# SSX.net
KiCad netlist of a schematic drawn in EAGLE
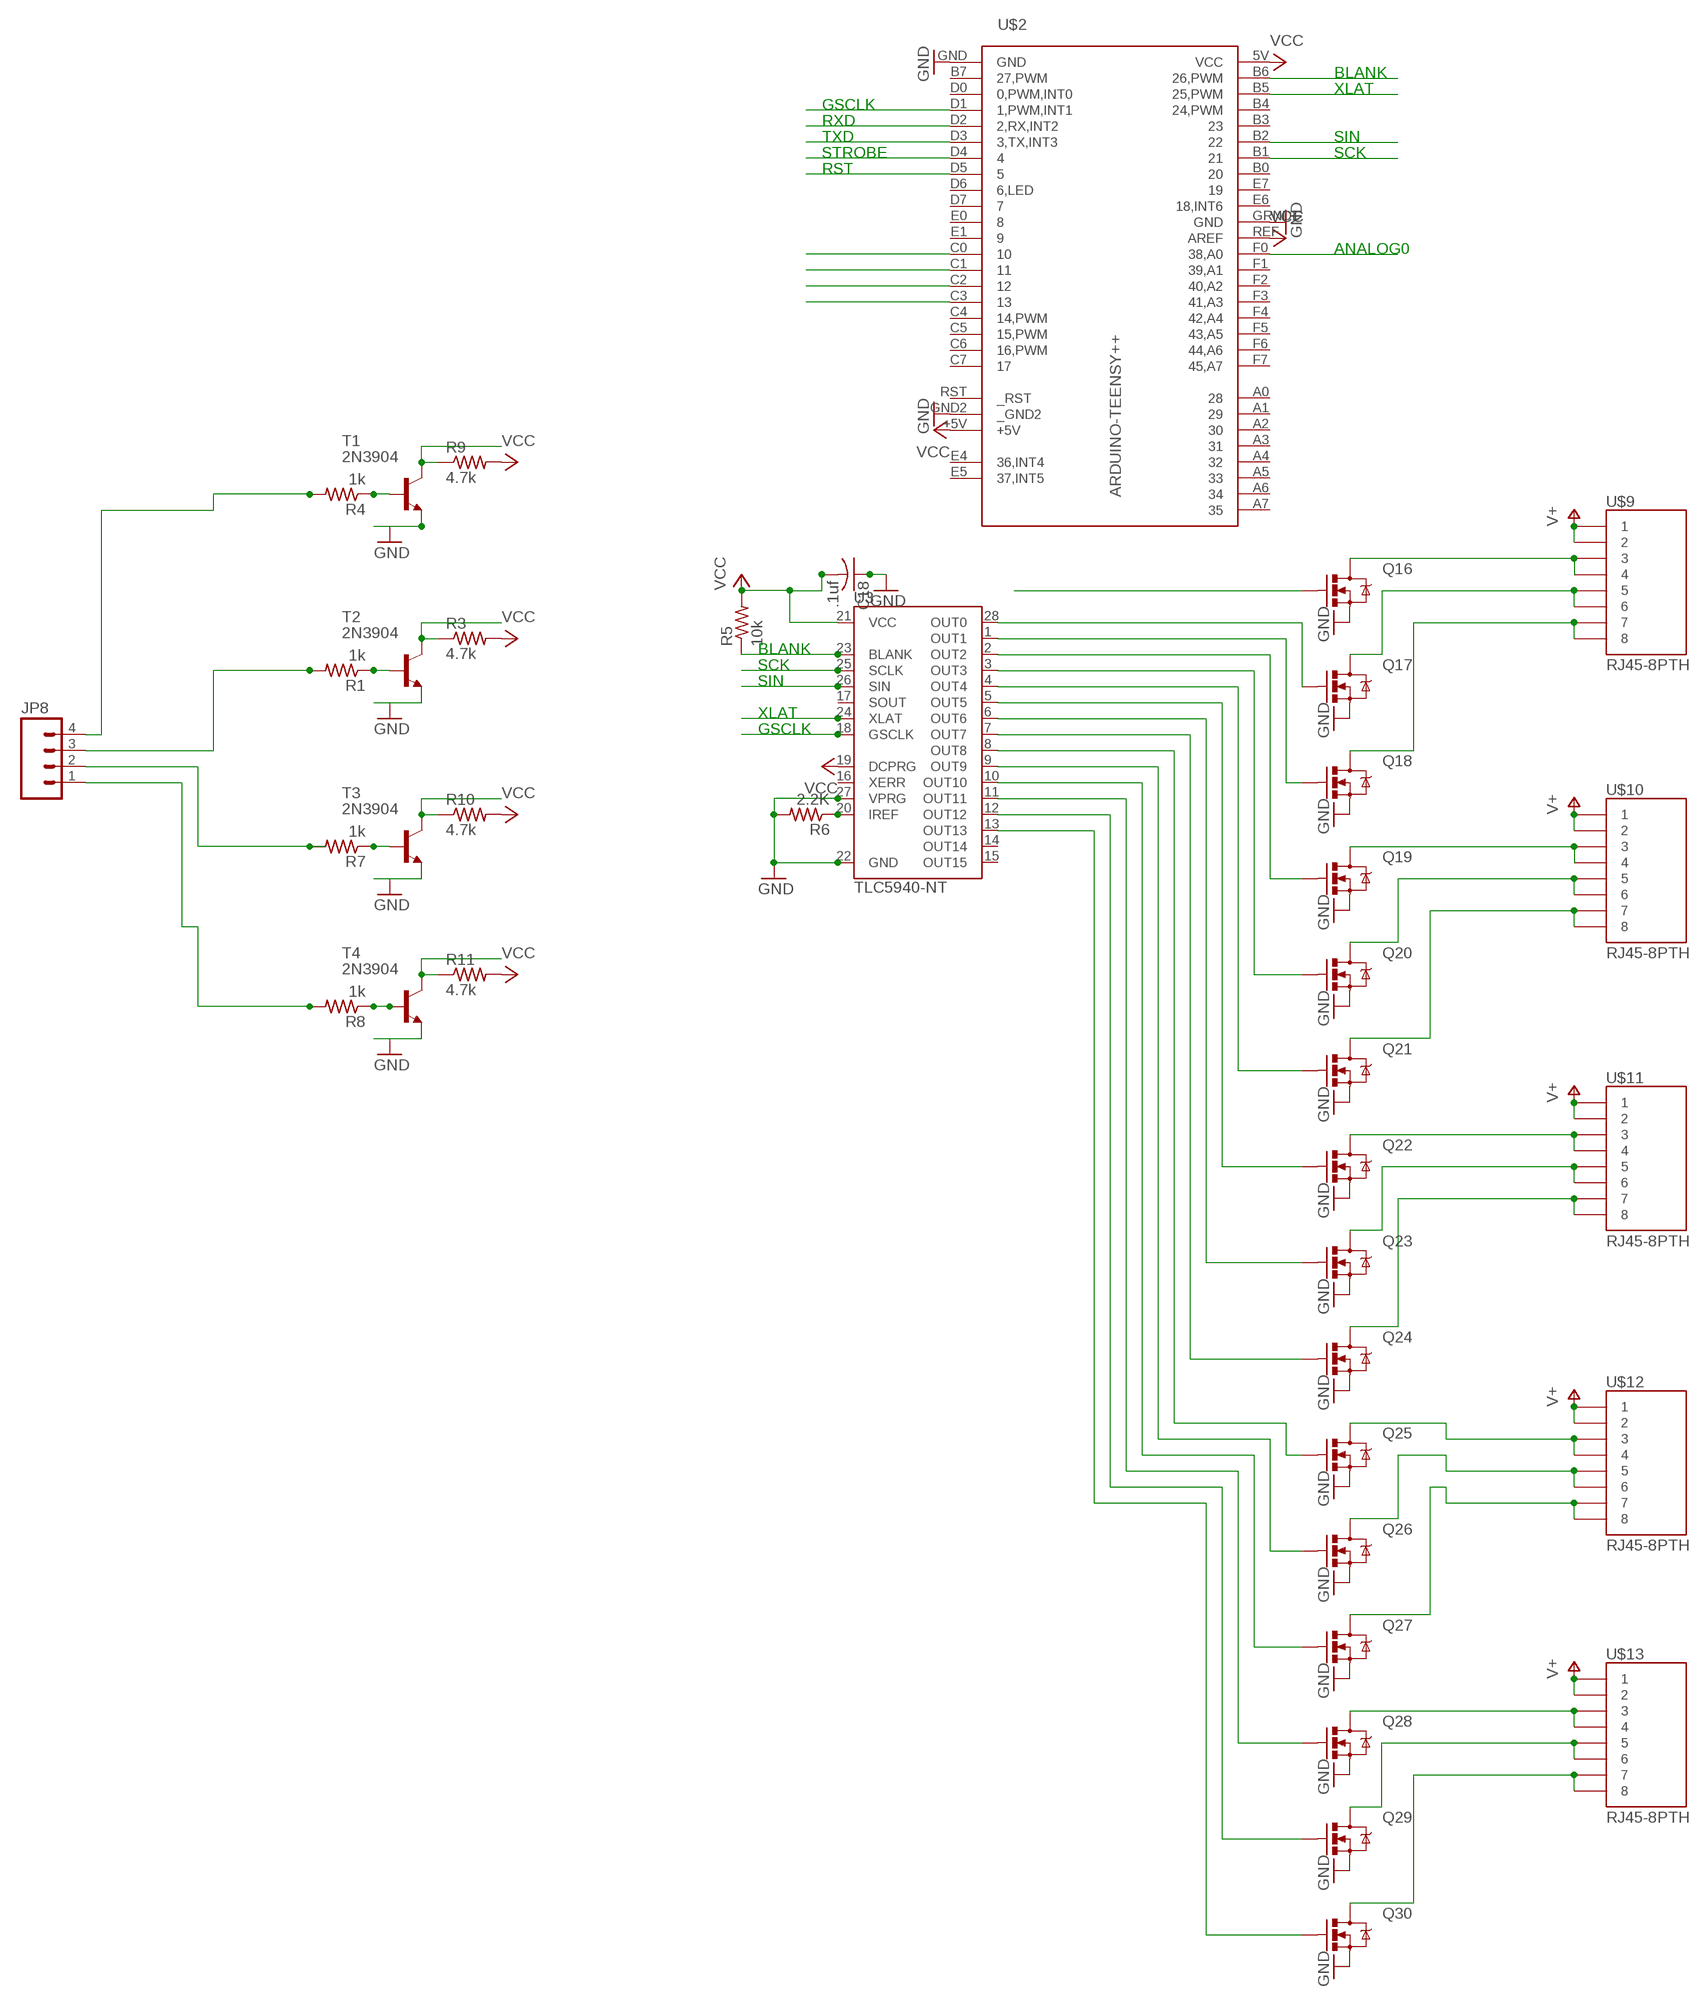
[diagram p0: schematic, sheet 1, part 1 of 2]
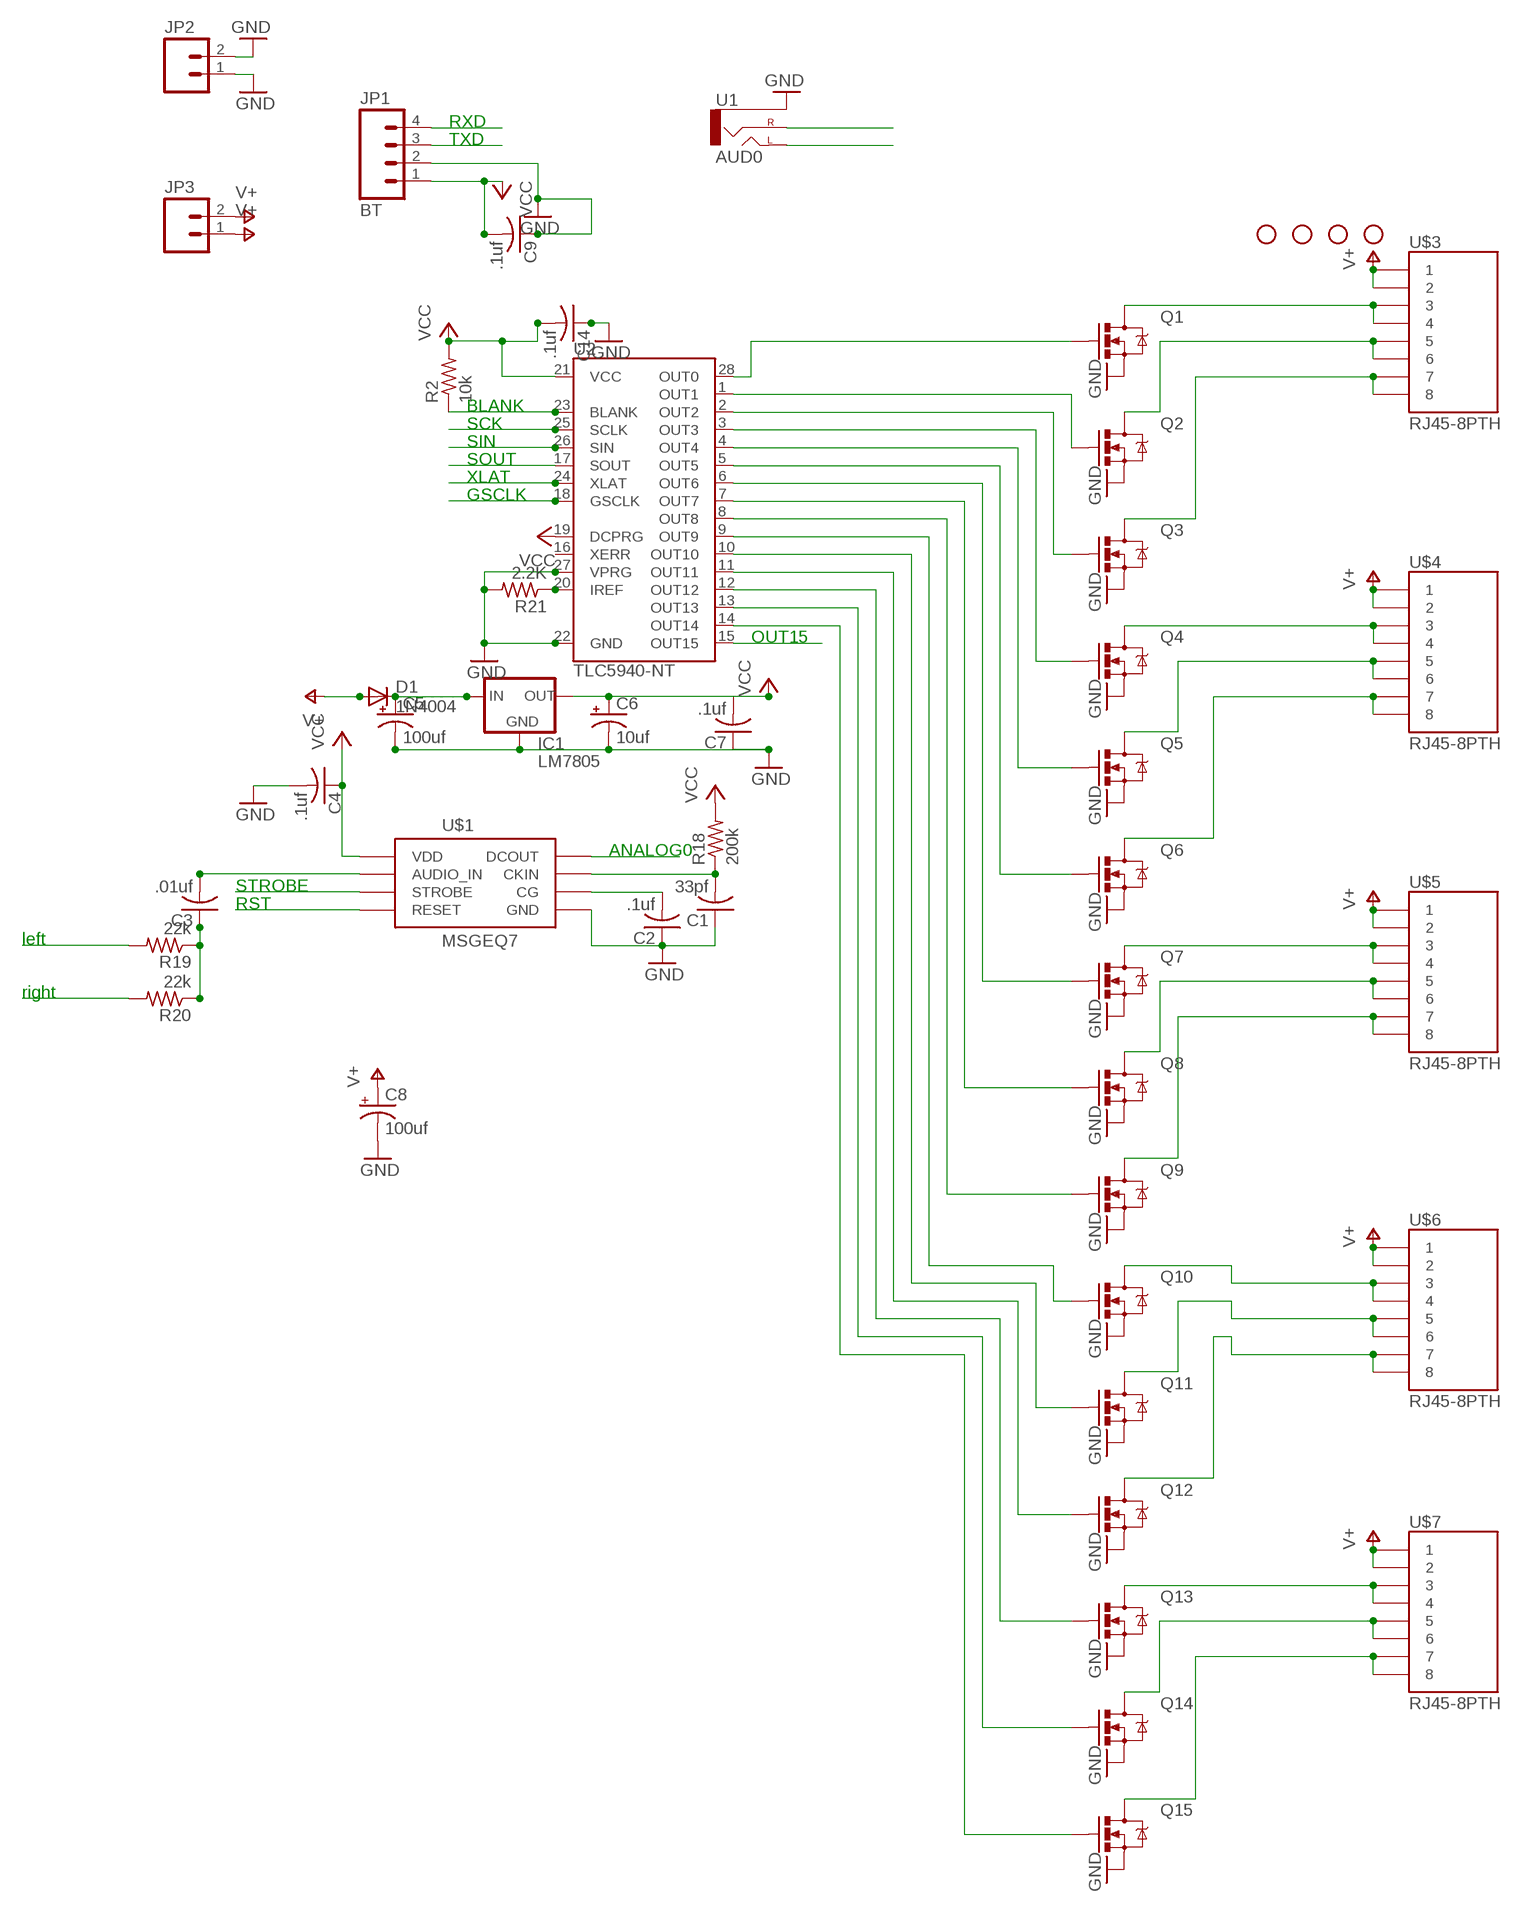
[diagram p1: schematic, sheet 1, part 2 of 2]

(export (version "E")
  (design (tool "Eeschema 10.0.6"))
  (components
    (comp (ref "C1")
      (value "33pf")
      (footprint "eagle-import:C025-025X050")
      (libsource (lib "eagle-import") (part "C-US025-025X050"))
    )
    (comp (ref "C2")
      (value ".1uf")
      (footprint "eagle-import:C025-025X050")
      (libsource (lib "eagle-import") (part "C-US025-025X050"))
    )
    (comp (ref "C3")
      (value ".01uf")
      (footprint "eagle-import:C025-025X050")
      (libsource (lib "eagle-import") (part "C-US025-025X050"))
    )
    (comp (ref "C4")
      (value ".1uf")
      (footprint "eagle-import:C025-025X050")
      (libsource (lib "eagle-import") (part "C-US025-025X050"))
    )
    (comp (ref "C5")
      (value "100uf")
      (footprint "eagle-import:CPOL-RADIAL-100UF-25V")
      (libsource (lib "eagle-import") (part "CAP_POLPTH1"))
    )
    (comp (ref "C6")
      (value "10uf")
      (footprint "eagle-import:CPOL-RADIAL-10UF-25V")
      (libsource (lib "eagle-import") (part "CAP_POLPTH2"))
    )
    (comp (ref "C7")
      (value ".1uf")
      (footprint "eagle-import:C025-025X050")
      (libsource (lib "eagle-import") (part "C-US025-025X050"))
    )
    (comp (ref "C8")
      (value "100uf")
      (footprint "eagle-import:CPOL-RADIAL-100UF-25V")
      (libsource (lib "eagle-import") (part "CAP_POLPTH1"))
    )
    (comp (ref "C9")
      (value ".1uf")
      (footprint "eagle-import:C025-025X050")
      (libsource (lib "eagle-import") (part "C-US025-025X050"))
    )
    (comp (ref "C14")
      (value ".1uf")
      (footprint "eagle-import:C025-025X050")
      (libsource (lib "eagle-import") (part "C-US025-025X050"))
    )
    (comp (ref "C18")
      (value ".1uf")
      (footprint "eagle-import:C025-025X050")
      (libsource (lib "eagle-import") (part "C-US025-025X050"))
    )
    (comp (ref "D1")
      (value "1N4004")
      (footprint "eagle-import:DIODE-1N4001")
      (libsource (lib "eagle-import") (part "DIODEPTH"))
    )
    (comp (ref "IC1")
      (value "LM7805")
      (footprint "eagle-import:TO220-IGO")
      (libsource (lib "eagle-import") (part "V_REG_78XXSINK"))
    )
    (comp (ref "JP1")
      (value "BT")
      (footprint "eagle-import:1X04_LOCK")
      (libsource (lib "eagle-import") (part "M04LOCK"))
    )
    (comp (ref "JP2")
      (value "M025MM")
      (footprint "eagle-import:SCREWTERMINAL-5MM-2")
      (libsource (lib "eagle-import") (part "M025MM"))
    )
    (comp (ref "JP3")
      (value "M025MM")
      (footprint "eagle-import:SCREWTERMINAL-5MM-2")
      (libsource (lib "eagle-import") (part "M025MM"))
    )
    (comp (ref "JP4")
      (value "STAND-OFF")
      (footprint "eagle-import:STAND-OFF")
      (libsource (lib "eagle-import") (part "STAND-OFF"))
    )
    (comp (ref "JP5")
      (value "STAND-OFF")
      (footprint "eagle-import:STAND-OFF")
      (libsource (lib "eagle-import") (part "STAND-OFF"))
    )
    (comp (ref "JP6")
      (value "STAND-OFF")
      (footprint "eagle-import:STAND-OFF")
      (libsource (lib "eagle-import") (part "STAND-OFF"))
    )
    (comp (ref "JP7")
      (value "STAND-OFF")
      (footprint "eagle-import:STAND-OFF")
      (libsource (lib "eagle-import") (part "STAND-OFF"))
    )
    (comp (ref "JP8")
      (value "M04PTH")
      (footprint "eagle-import:1X04")
      (libsource (lib "eagle-import") (part "SparkFun-Connectors_M04PTH"))
    )
    (comp (ref "Q1")
      (value "MOSFET-NCHANNELPTH2")
      (footprint "eagle-import:TO220V")
      (libsource (lib "eagle-import") (part "MOSFET-NCHANNELPTH2"))
    )
    (comp (ref "Q2")
      (value "MOSFET-NCHANNELPTH2")
      (footprint "eagle-import:TO220V")
      (libsource (lib "eagle-import") (part "MOSFET-NCHANNELPTH2"))
    )
    (comp (ref "Q3")
      (value "MOSFET-NCHANNELPTH2")
      (footprint "eagle-import:TO220V")
      (libsource (lib "eagle-import") (part "MOSFET-NCHANNELPTH2"))
    )
    (comp (ref "Q4")
      (value "MOSFET-NCHANNELPTH2")
      (footprint "eagle-import:TO220V")
      (libsource (lib "eagle-import") (part "MOSFET-NCHANNELPTH2"))
    )
    (comp (ref "Q5")
      (value "MOSFET-NCHANNELPTH2")
      (footprint "eagle-import:TO220V")
      (libsource (lib "eagle-import") (part "MOSFET-NCHANNELPTH2"))
    )
    (comp (ref "Q6")
      (value "MOSFET-NCHANNELPTH2")
      (footprint "eagle-import:TO220V")
      (libsource (lib "eagle-import") (part "MOSFET-NCHANNELPTH2"))
    )
    (comp (ref "Q7")
      (value "MOSFET-NCHANNELPTH2")
      (footprint "eagle-import:TO220V")
      (libsource (lib "eagle-import") (part "MOSFET-NCHANNELPTH2"))
    )
    (comp (ref "Q8")
      (value "MOSFET-NCHANNELPTH2")
      (footprint "eagle-import:TO220V")
      (libsource (lib "eagle-import") (part "MOSFET-NCHANNELPTH2"))
    )
    (comp (ref "Q9")
      (value "MOSFET-NCHANNELPTH2")
      (footprint "eagle-import:TO220V")
      (libsource (lib "eagle-import") (part "MOSFET-NCHANNELPTH2"))
    )
    (comp (ref "Q10")
      (value "MOSFET-NCHANNELPTH2")
      (footprint "eagle-import:TO220V")
      (libsource (lib "eagle-import") (part "MOSFET-NCHANNELPTH2"))
    )
    (comp (ref "Q11")
      (value "MOSFET-NCHANNELPTH2")
      (footprint "eagle-import:TO220V")
      (libsource (lib "eagle-import") (part "MOSFET-NCHANNELPTH2"))
    )
    (comp (ref "Q12")
      (value "MOSFET-NCHANNELPTH2")
      (footprint "eagle-import:TO220V")
      (libsource (lib "eagle-import") (part "MOSFET-NCHANNELPTH2"))
    )
    (comp (ref "Q13")
      (value "MOSFET-NCHANNELPTH2")
      (footprint "eagle-import:TO220V")
      (libsource (lib "eagle-import") (part "MOSFET-NCHANNELPTH2"))
    )
    (comp (ref "Q14")
      (value "MOSFET-NCHANNELPTH2")
      (footprint "eagle-import:TO220V")
      (libsource (lib "eagle-import") (part "MOSFET-NCHANNELPTH2"))
    )
    (comp (ref "Q15")
      (value "MOSFET-NCHANNELPTH2")
      (footprint "eagle-import:TO220V")
      (libsource (lib "eagle-import") (part "MOSFET-NCHANNELPTH2"))
    )
    (comp (ref "Q16")
      (value "MOSFET-NCHANNELPTH2")
      (footprint "eagle-import:TO220V")
      (libsource (lib "eagle-import") (part "MOSFET-NCHANNELPTH2"))
    )
    (comp (ref "Q17")
      (value "MOSFET-NCHANNELPTH2")
      (footprint "eagle-import:TO220V")
      (libsource (lib "eagle-import") (part "MOSFET-NCHANNELPTH2"))
    )
    (comp (ref "Q18")
      (value "MOSFET-NCHANNELPTH2")
      (footprint "eagle-import:TO220V")
      (libsource (lib "eagle-import") (part "MOSFET-NCHANNELPTH2"))
    )
    (comp (ref "Q19")
      (value "MOSFET-NCHANNELPTH2")
      (footprint "eagle-import:TO220V")
      (libsource (lib "eagle-import") (part "MOSFET-NCHANNELPTH2"))
    )
    (comp (ref "Q20")
      (value "MOSFET-NCHANNELPTH2")
      (footprint "eagle-import:TO220V")
      (libsource (lib "eagle-import") (part "MOSFET-NCHANNELPTH2"))
    )
    (comp (ref "Q21")
      (value "MOSFET-NCHANNELPTH2")
      (footprint "eagle-import:TO220V")
      (libsource (lib "eagle-import") (part "MOSFET-NCHANNELPTH2"))
    )
    (comp (ref "Q22")
      (value "MOSFET-NCHANNELPTH2")
      (footprint "eagle-import:TO220V")
      (libsource (lib "eagle-import") (part "MOSFET-NCHANNELPTH2"))
    )
    (comp (ref "Q23")
      (value "MOSFET-NCHANNELPTH2")
      (footprint "eagle-import:TO220V")
      (libsource (lib "eagle-import") (part "MOSFET-NCHANNELPTH2"))
    )
    (comp (ref "Q24")
      (value "MOSFET-NCHANNELPTH2")
      (footprint "eagle-import:TO220V")
      (libsource (lib "eagle-import") (part "MOSFET-NCHANNELPTH2"))
    )
    (comp (ref "Q25")
      (value "MOSFET-NCHANNELPTH2")
      (footprint "eagle-import:TO220V")
      (libsource (lib "eagle-import") (part "MOSFET-NCHANNELPTH2"))
    )
    (comp (ref "Q26")
      (value "MOSFET-NCHANNELPTH2")
      (footprint "eagle-import:TO220V")
      (libsource (lib "eagle-import") (part "MOSFET-NCHANNELPTH2"))
    )
    (comp (ref "Q27")
      (value "MOSFET-NCHANNELPTH2")
      (footprint "eagle-import:TO220V")
      (libsource (lib "eagle-import") (part "MOSFET-NCHANNELPTH2"))
    )
    (comp (ref "Q28")
      (value "MOSFET-NCHANNELPTH2")
      (footprint "eagle-import:TO220V")
      (libsource (lib "eagle-import") (part "MOSFET-NCHANNELPTH2"))
    )
    (comp (ref "Q29")
      (value "MOSFET-NCHANNELPTH2")
      (footprint "eagle-import:TO220V")
      (libsource (lib "eagle-import") (part "MOSFET-NCHANNELPTH2"))
    )
    (comp (ref "Q30")
      (value "MOSFET-NCHANNELPTH2")
      (footprint "eagle-import:TO220V")
      (libsource (lib "eagle-import") (part "MOSFET-NCHANNELPTH2"))
    )
    (comp (ref "R1")
      (value "1k")
      (footprint "eagle-import:0207_2V")
      (libsource (lib "eagle-import") (part "R-US_0207/2V"))
    )
    (comp (ref "R2")
      (value "10k")
      (footprint "eagle-import:0207_2V")
      (libsource (lib "eagle-import") (part "R-US_0207/2V"))
    )
    (comp (ref "R3")
      (value "4.7k")
      (footprint "eagle-import:0207_2V")
      (libsource (lib "eagle-import") (part "R-US_0207/2V"))
    )
    (comp (ref "R4")
      (value "1k")
      (footprint "eagle-import:0207_2V")
      (libsource (lib "eagle-import") (part "R-US_0207/2V"))
    )
    (comp (ref "R5")
      (value "10k")
      (footprint "eagle-import:0207_2V")
      (libsource (lib "eagle-import") (part "R-US_0207/2V"))
    )
    (comp (ref "R6")
      (value "2.2K")
      (footprint "eagle-import:0207_2V")
      (libsource (lib "eagle-import") (part "R-US_0207/2V"))
    )
    (comp (ref "R7")
      (value "1k")
      (footprint "eagle-import:0207_2V")
      (libsource (lib "eagle-import") (part "R-US_0207/2V"))
    )
    (comp (ref "R8")
      (value "1k")
      (footprint "eagle-import:0207_2V")
      (libsource (lib "eagle-import") (part "R-US_0207/2V"))
    )
    (comp (ref "R9")
      (value "4.7k")
      (footprint "eagle-import:0207_2V")
      (libsource (lib "eagle-import") (part "R-US_0207/2V"))
    )
    (comp (ref "R10")
      (value "4.7k")
      (footprint "eagle-import:0207_2V")
      (libsource (lib "eagle-import") (part "R-US_0207/2V"))
    )
    (comp (ref "R11")
      (value "4.7k")
      (footprint "eagle-import:0207_2V")
      (libsource (lib "eagle-import") (part "R-US_0207/2V"))
    )
    (comp (ref "R18")
      (value "200k")
      (footprint "eagle-import:0207_2V")
      (libsource (lib "eagle-import") (part "R-US_0207/2V"))
    )
    (comp (ref "R19")
      (value "22k")
      (footprint "eagle-import:0207_2V")
      (libsource (lib "eagle-import") (part "R-US_0207/2V"))
    )
    (comp (ref "R20")
      (value "22k")
      (footprint "eagle-import:0207_2V")
      (libsource (lib "eagle-import") (part "R-US_0207/2V"))
    )
    (comp (ref "R21")
      (value "2.2K")
      (footprint "eagle-import:0207_2V")
      (libsource (lib "eagle-import") (part "R-US_0207/2V"))
    )
    (comp (ref "T1")
      (value "2N3904")
      (footprint "eagle-import:TO92")
      (libsource (lib "eagle-import") (part "2N3904"))
    )
    (comp (ref "T2")
      (value "2N3904")
      (footprint "eagle-import:TO92")
      (libsource (lib "eagle-import") (part "2N3904"))
    )
    (comp (ref "T3")
      (value "2N3904")
      (footprint "eagle-import:TO92")
      (libsource (lib "eagle-import") (part "2N3904"))
    )
    (comp (ref "T4")
      (value "2N3904")
      (footprint "eagle-import:TO92")
      (libsource (lib "eagle-import") (part "2N3904"))
    )
    (comp (ref "U$1")
      (value "MSGEQ7_PTH")
      (footprint "eagle-import:DIL08")
      (libsource (lib "eagle-import") (part "MSGEQ7_PTH"))
    )
    (comp (ref "U$2")
      (value "ARDUINO-TEENSY++")
      (footprint "eagle-import:TEENSY++")
      (libsource (lib "eagle-import") (part "ARDUINO-TEENSY++"))
    )
    (comp (ref "U$3")
      (value "RJ45-8PTH")
      (footprint "eagle-import:RJ45-8")
      (libsource (lib "eagle-import") (part "RJ45-8PTH"))
    )
    (comp (ref "U$4")
      (value "RJ45-8PTH")
      (footprint "eagle-import:RJ45-8")
      (libsource (lib "eagle-import") (part "RJ45-8PTH"))
    )
    (comp (ref "U$5")
      (value "RJ45-8PTH")
      (footprint "eagle-import:RJ45-8")
      (libsource (lib "eagle-import") (part "RJ45-8PTH"))
    )
    (comp (ref "U$6")
      (value "RJ45-8PTH")
      (footprint "eagle-import:RJ45-8")
      (libsource (lib "eagle-import") (part "RJ45-8PTH"))
    )
    (comp (ref "U$7")
      (value "RJ45-8PTH")
      (footprint "eagle-import:RJ45-8")
      (libsource (lib "eagle-import") (part "RJ45-8PTH"))
    )
    (comp (ref "U$9")
      (value "RJ45-8PTH")
      (footprint "eagle-import:RJ45-8")
      (libsource (lib "eagle-import") (part "RJ45-8PTH"))
    )
    (comp (ref "U$10")
      (value "RJ45-8PTH")
      (footprint "eagle-import:RJ45-8")
      (libsource (lib "eagle-import") (part "RJ45-8PTH"))
    )
    (comp (ref "U$11")
      (value "RJ45-8PTH")
      (footprint "eagle-import:RJ45-8")
      (libsource (lib "eagle-import") (part "RJ45-8PTH"))
    )
    (comp (ref "U$12")
      (value "RJ45-8PTH")
      (footprint "eagle-import:RJ45-8")
      (libsource (lib "eagle-import") (part "RJ45-8PTH"))
    )
    (comp (ref "U$13")
      (value "RJ45-8PTH")
      (footprint "eagle-import:RJ45-8")
      (libsource (lib "eagle-import") (part "RJ45-8PTH"))
    )
    (comp (ref "U1")
      (value "AUD0")
      (footprint "eagle-import:AUDIO-JACK")
      (libsource (lib "eagle-import") (part "AUDIO-JACKPTH"))
    )
    (comp (ref "U2")
      (value "TLC5940-NT")
      (footprint "eagle-import:DIL28-3")
      (libsource (lib "eagle-import") (part "TLC5940-NT"))
    )
    (comp (ref "U3")
      (value "TLC5940-NT")
      (footprint "eagle-import:DIL28-3")
      (libsource (lib "eagle-import") (part "TLC5940-NT"))
    )
  )
  (nets
    (net (code "1") (name "/ANALOG0") (class "Default")
      (node (ref "U$1") (pin "3") (pinfunction "DCOUT_3") (pintype "bidirectional"))
      (node (ref "U$2") (pin "F0") (pinfunction "38,A0_F0") (pintype "bidirectional"))
    )
    (net (code "2") (name "/ARS") (class "Default")
      (node (ref "U$1") (pin "7") (pinfunction "RESET_7") (pintype "input"))
      (node (ref "U$2") (pin "D5") (pinfunction "5_D5") (pintype "bidirectional"))
    )
    (net (code "3") (name "/BL") (class "Default")
      (node (ref "R10") (pin "1") (pinfunction "1_1") (pintype "passive"))
      (node (ref "T3") (pin "1") (pinfunction "C_1") (pintype "passive"))
      (node (ref "U$2") (pin "C1") (pinfunction "11_C1") (pintype "bidirectional"))
    )
    (net (code "4") (name "/BLANK") (class "Default")
      (node (ref "R2") (pin "1") (pinfunction "1_1") (pintype "passive"))
      (node (ref "U$2") (pin "B6") (pinfunction "26,PWM_B6") (pintype "bidirectional"))
      (node (ref "U2") (pin "23") (pinfunction "BLANK_23") (pintype "bidirectional"))
    )
    (net (code "5") (name "/GSCLK") (class "Default")
      (node (ref "U$2") (pin "D1") (pinfunction "1,PWM,INT1_D1") (pintype "bidirectional"))
      (node (ref "U2") (pin "18") (pinfunction "GSCLK_18") (pintype "bidirectional"))
    )
    (net (code "6") (name "/HL") (class "Default")
      (node (ref "R11") (pin "1") (pinfunction "1_1") (pintype "passive"))
      (node (ref "T4") (pin "1") (pinfunction "C_1") (pintype "passive"))
      (node (ref "U$2") (pin "C0") (pinfunction "10_C0") (pintype "bidirectional"))
    )
    (net (code "7") (name "/LEFT") (class "Default")
      (node (ref "R19") (pin "2") (pinfunction "2_2") (pintype "passive"))
      (node (ref "U1") (pin "TIP") (pinfunction "LEFT_TIP") (pintype "bidirectional"))
    )
    (net (code "8") (name "/LTS") (class "Default")
      (node (ref "R3") (pin "1") (pinfunction "1_1") (pintype "passive"))
      (node (ref "T2") (pin "1") (pinfunction "C_1") (pintype "passive"))
      (node (ref "U$2") (pin "C2") (pinfunction "12_C2") (pintype "bidirectional"))
    )
    (net (code "9") (name "/OUT15") (class "Default")
      (node (ref "Q16") (pin "1") (pinfunction "G_1") (pintype "passive"))
      (node (ref "U2") (pin "15") (pinfunction "OUT15_15") (pintype "bidirectional"))
    )
    (net (code "10") (name "/RIGHT") (class "Default")
      (node (ref "R20") (pin "2") (pinfunction "2_2") (pintype "passive"))
      (node (ref "U1") (pin "RING") (pinfunction "RIGHT_RING") (pintype "bidirectional"))
    )
    (net (code "11") (name "/RTS") (class "Default")
      (node (ref "R9") (pin "1") (pinfunction "1_1") (pintype "passive"))
      (node (ref "T1") (pin "1") (pinfunction "C_1") (pintype "passive"))
      (node (ref "U$2") (pin "C3") (pinfunction "13_C3") (pintype "bidirectional"))
    )
    (net (code "12") (name "/RXD") (class "Default")
      (node (ref "JP1") (pin "4") (pinfunction "4_4") (pintype "passive"))
      (node (ref "U$2") (pin "D3") (pinfunction "3,TX,INT3_D3") (pintype "bidirectional"))
    )
    (net (code "13") (name "/SCK") (class "Default")
      (node (ref "U$2") (pin "B1") (pinfunction "21_B1") (pintype "bidirectional"))
      (node (ref "U2") (pin "25") (pinfunction "SCLK_25") (pintype "bidirectional"))
    )
    (net (code "14") (name "/SIN") (class "Default")
      (node (ref "U$2") (pin "B2") (pinfunction "22_B2") (pintype "bidirectional"))
      (node (ref "U2") (pin "26") (pinfunction "SIN_26") (pintype "bidirectional"))
    )
    (net (code "15") (name "/SOUT") (class "Default")
      (node (ref "U2") (pin "17") (pinfunction "SOUT_17") (pintype "bidirectional"))
      (node (ref "U3") (pin "26") (pinfunction "SIN_26") (pintype "bidirectional"))
    )
    (net (code "16") (name "/STROBE") (class "Default")
      (node (ref "U$1") (pin "4") (pinfunction "STROBE_4") (pintype "input"))
      (node (ref "U$2") (pin "D4") (pinfunction "4_D4") (pintype "bidirectional"))
    )
    (net (code "17") (name "/TXD") (class "Default")
      (node (ref "JP1") (pin "3") (pinfunction "3_3") (pintype "passive"))
      (node (ref "U$2") (pin "D2") (pinfunction "2,RX,INT2_D2") (pintype "bidirectional"))
    )
    (net (code "18") (name "/XLAT") (class "Default")
      (node (ref "U$2") (pin "B5") (pinfunction "25,PWM_B5") (pintype "bidirectional"))
      (node (ref "U2") (pin "24") (pinfunction "XLAT_24") (pintype "bidirectional"))
    )
    (net (code "19") (name "GND") (class "Default")
      (node (ref "C1") (pin "1") (pinfunction "1_1") (pintype "passive"))
      (node (ref "C14") (pin "1") (pinfunction "1_1") (pintype "passive"))
      (node (ref "C18") (pin "1") (pinfunction "1_1") (pintype "passive"))
      (node (ref "C2") (pin "1") (pinfunction "1_1") (pintype "passive"))
      (node (ref "C4") (pin "2") (pinfunction "2_2") (pintype "passive"))
      (node (ref "C5") (pin "2") (pinfunction "-_2") (pintype "passive"))
      (node (ref "C6") (pin "2") (pinfunction "-_2") (pintype "passive"))
      (node (ref "C7") (pin "1") (pinfunction "1_1") (pintype "passive"))
      (node (ref "C8") (pin "2") (pinfunction "-_2") (pintype "passive"))
      (node (ref "C9") (pin "1") (pinfunction "1_1") (pintype "passive"))
      (node (ref "IC1") (pin "GND") (pinfunction "GND_GND") (pintype "input"))
      (node (ref "JP1") (pin "2") (pinfunction "2_2") (pintype "passive"))
      (node (ref "JP2") (pin "1") (pinfunction "1_1") (pintype "passive"))
      (node (ref "JP2") (pin "2") (pinfunction "2_2") (pintype "passive"))
      (node (ref "Q1") (pin "3") (pinfunction "S_3") (pintype "passive"))
      (node (ref "Q10") (pin "3") (pinfunction "S_3") (pintype "passive"))
      (node (ref "Q11") (pin "3") (pinfunction "S_3") (pintype "passive"))
      (node (ref "Q12") (pin "3") (pinfunction "S_3") (pintype "passive"))
      (node (ref "Q13") (pin "3") (pinfunction "S_3") (pintype "passive"))
      (node (ref "Q14") (pin "3") (pinfunction "S_3") (pintype "passive"))
      (node (ref "Q15") (pin "3") (pinfunction "S_3") (pintype "passive"))
      (node (ref "Q16") (pin "3") (pinfunction "S_3") (pintype "passive"))
      (node (ref "Q17") (pin "3") (pinfunction "S_3") (pintype "passive"))
      (node (ref "Q18") (pin "3") (pinfunction "S_3") (pintype "passive"))
      (node (ref "Q19") (pin "3") (pinfunction "S_3") (pintype "passive"))
      (node (ref "Q2") (pin "3") (pinfunction "S_3") (pintype "passive"))
      (node (ref "Q20") (pin "3") (pinfunction "S_3") (pintype "passive"))
      (node (ref "Q21") (pin "3") (pinfunction "S_3") (pintype "passive"))
      (node (ref "Q22") (pin "3") (pinfunction "S_3") (pintype "passive"))
      (node (ref "Q23") (pin "3") (pinfunction "S_3") (pintype "passive"))
      (node (ref "Q24") (pin "3") (pinfunction "S_3") (pintype "passive"))
      (node (ref "Q25") (pin "3") (pinfunction "S_3") (pintype "passive"))
      (node (ref "Q26") (pin "3") (pinfunction "S_3") (pintype "passive"))
      (node (ref "Q27") (pin "3") (pinfunction "S_3") (pintype "passive"))
      (node (ref "Q28") (pin "3") (pinfunction "S_3") (pintype "passive"))
      (node (ref "Q29") (pin "3") (pinfunction "S_3") (pintype "passive"))
      (node (ref "Q3") (pin "3") (pinfunction "S_3") (pintype "passive"))
      (node (ref "Q30") (pin "3") (pinfunction "S_3") (pintype "passive"))
      (node (ref "Q4") (pin "3") (pinfunction "S_3") (pintype "passive"))
      (node (ref "Q5") (pin "3") (pinfunction "S_3") (pintype "passive"))
      (node (ref "Q6") (pin "3") (pinfunction "S_3") (pintype "passive"))
      (node (ref "Q7") (pin "3") (pinfunction "S_3") (pintype "passive"))
      (node (ref "Q8") (pin "3") (pinfunction "S_3") (pintype "passive"))
      (node (ref "Q9") (pin "3") (pinfunction "S_3") (pintype "passive"))
      (node (ref "R21") (pin "2") (pinfunction "2_2") (pintype "passive"))
      (node (ref "R6") (pin "2") (pinfunction "2_2") (pintype "passive"))
      (node (ref "U$1") (pin "2") (pinfunction "GND_2") (pintype "bidirectional"))
      (node (ref "U$2") (pin "GND") (pinfunction "GND_GND") (pintype "power_in"))
      (node (ref "U$2") (pin "GND2") (pinfunction "_GND2_GND2") (pintype "power_in"))
      (node (ref "U$2") (pin "GRND1") (pinfunction "GND_GRND1") (pintype "power_in"))
      (node (ref "U1") (pin "SLEEVE") (pinfunction "SLEEVE_SLEEVE") (pintype "bidirectional"))
      (node (ref "U2") (pin "22") (pinfunction "GND_22") (pintype "bidirectional"))
      (node (ref "U2") (pin "27") (pinfunction "VPRG_27") (pintype "bidirectional"))
      (node (ref "U3") (pin "22") (pinfunction "GND_22") (pintype "bidirectional"))
      (node (ref "U3") (pin "27") (pinfunction "VPRG_27") (pintype "bidirectional"))
    )
    (net (code "20") (name "Net-(C3-Pad1)") (class "Default")
      (node (ref "C3") (pin "1") (pinfunction "1_1") (pintype "passive"))
      (node (ref "R19") (pin "1") (pinfunction "1_1") (pintype "passive"))
      (node (ref "R20") (pin "1") (pinfunction "1_1") (pintype "passive"))
    )
    (net (code "21") (name "Net-(C5-+)") (class "Default")
      (node (ref "C5") (pin "1") (pinfunction "+_1") (pintype "passive"))
      (node (ref "D1") (pin "C") (pinfunction "C_C") (pintype "passive"))
      (node (ref "IC1") (pin "IN") (pinfunction "IN_IN") (pintype "input"))
    )
    (net (code "22") (name "Net-(JP8-Pad1)") (class "Default")
      (node (ref "JP8") (pin "1") (pinfunction "1_1") (pintype "passive"))
      (node (ref "R8") (pin "2") (pinfunction "2_2") (pintype "passive"))
    )
    (net (code "23") (name "Net-(JP8-Pad2)") (class "Default")
      (node (ref "JP8") (pin "2") (pinfunction "2_2") (pintype "passive"))
      (node (ref "R7") (pin "2") (pinfunction "2_2") (pintype "passive"))
    )
    (net (code "24") (name "Net-(JP8-Pad3)") (class "Default")
      (node (ref "JP8") (pin "3") (pinfunction "3_3") (pintype "passive"))
      (node (ref "R1") (pin "2") (pinfunction "2_2") (pintype "passive"))
    )
    (net (code "25") (name "Net-(JP8-Pad4)") (class "Default")
      (node (ref "JP8") (pin "4") (pinfunction "4_4") (pintype "passive"))
      (node (ref "R4") (pin "2") (pinfunction "2_2") (pintype "passive"))
    )
    (net (code "26") (name "Net-(Q1-D)") (class "Default")
      (node (ref "Q1") (pin "2") (pinfunction "D_2") (pintype "passive"))
      (node (ref "U$3") (pin "3") (pinfunction "3_3") (pintype "bidirectional"))
      (node (ref "U$3") (pin "4") (pinfunction "4_4") (pintype "bidirectional"))
    )
    (net (code "27") (name "Net-(Q1-G)") (class "Default")
      (node (ref "Q1") (pin "1") (pinfunction "G_1") (pintype "passive"))
      (node (ref "U2") (pin "28") (pinfunction "OUT0_28") (pintype "bidirectional"))
    )
    (net (code "28") (name "Net-(Q2-D)") (class "Default")
      (node (ref "Q2") (pin "2") (pinfunction "D_2") (pintype "passive"))
      (node (ref "U$3") (pin "5") (pinfunction "5_5") (pintype "bidirectional"))
      (node (ref "U$3") (pin "6") (pinfunction "6_6") (pintype "bidirectional"))
    )
    (net (code "29") (name "Net-(Q2-G)") (class "Default")
      (node (ref "Q2") (pin "1") (pinfunction "G_1") (pintype "passive"))
      (node (ref "U2") (pin "1") (pinfunction "OUT1_1") (pintype "bidirectional"))
    )
    (net (code "30") (name "Net-(Q3-D)") (class "Default")
      (node (ref "Q3") (pin "2") (pinfunction "D_2") (pintype "passive"))
      (node (ref "U$3") (pin "7") (pinfunction "7_7") (pintype "bidirectional"))
      (node (ref "U$3") (pin "8") (pinfunction "8_8") (pintype "bidirectional"))
    )
    (net (code "31") (name "Net-(Q3-G)") (class "Default")
      (node (ref "Q3") (pin "1") (pinfunction "G_1") (pintype "passive"))
      (node (ref "U2") (pin "2") (pinfunction "OUT2_2") (pintype "bidirectional"))
    )
    (net (code "32") (name "Net-(Q4-D)") (class "Default")
      (node (ref "Q4") (pin "2") (pinfunction "D_2") (pintype "passive"))
      (node (ref "U$4") (pin "3") (pinfunction "3_3") (pintype "bidirectional"))
      (node (ref "U$4") (pin "4") (pinfunction "4_4") (pintype "bidirectional"))
    )
    (net (code "33") (name "Net-(Q4-G)") (class "Default")
      (node (ref "Q4") (pin "1") (pinfunction "G_1") (pintype "passive"))
      (node (ref "U2") (pin "3") (pinfunction "OUT3_3") (pintype "bidirectional"))
    )
    (net (code "34") (name "Net-(Q5-D)") (class "Default")
      (node (ref "Q5") (pin "2") (pinfunction "D_2") (pintype "passive"))
      (node (ref "U$4") (pin "5") (pinfunction "5_5") (pintype "bidirectional"))
      (node (ref "U$4") (pin "6") (pinfunction "6_6") (pintype "bidirectional"))
    )
    (net (code "35") (name "Net-(Q5-G)") (class "Default")
      (node (ref "Q5") (pin "1") (pinfunction "G_1") (pintype "passive"))
      (node (ref "U2") (pin "4") (pinfunction "OUT4_4") (pintype "bidirectional"))
    )
    (net (code "36") (name "Net-(Q6-D)") (class "Default")
      (node (ref "Q6") (pin "2") (pinfunction "D_2") (pintype "passive"))
      (node (ref "U$4") (pin "7") (pinfunction "7_7") (pintype "bidirectional"))
      (node (ref "U$4") (pin "8") (pinfunction "8_8") (pintype "bidirectional"))
    )
    (net (code "37") (name "Net-(Q6-G)") (class "Default")
      (node (ref "Q6") (pin "1") (pinfunction "G_1") (pintype "passive"))
      (node (ref "U2") (pin "5") (pinfunction "OUT5_5") (pintype "bidirectional"))
    )
    (net (code "38") (name "Net-(Q7-D)") (class "Default")
      (node (ref "Q7") (pin "2") (pinfunction "D_2") (pintype "passive"))
      (node (ref "U$5") (pin "3") (pinfunction "3_3") (pintype "bidirectional"))
      (node (ref "U$5") (pin "4") (pinfunction "4_4") (pintype "bidirectional"))
    )
    (net (code "39") (name "Net-(Q7-G)") (class "Default")
      (node (ref "Q7") (pin "1") (pinfunction "G_1") (pintype "passive"))
      (node (ref "U2") (pin "6") (pinfunction "OUT6_6") (pintype "bidirectional"))
    )
    (net (code "40") (name "Net-(Q8-D)") (class "Default")
      (node (ref "Q8") (pin "2") (pinfunction "D_2") (pintype "passive"))
      (node (ref "U$5") (pin "5") (pinfunction "5_5") (pintype "bidirectional"))
      (node (ref "U$5") (pin "6") (pinfunction "6_6") (pintype "bidirectional"))
    )
    (net (code "41") (name "Net-(Q8-G)") (class "Default")
      (node (ref "Q8") (pin "1") (pinfunction "G_1") (pintype "passive"))
      (node (ref "U2") (pin "7") (pinfunction "OUT7_7") (pintype "bidirectional"))
    )
    (net (code "42") (name "Net-(Q9-D)") (class "Default")
      (node (ref "Q9") (pin "2") (pinfunction "D_2") (pintype "passive"))
      (node (ref "U$5") (pin "7") (pinfunction "7_7") (pintype "bidirectional"))
      (node (ref "U$5") (pin "8") (pinfunction "8_8") (pintype "bidirectional"))
    )
    (net (code "43") (name "Net-(Q9-G)") (class "Default")
      (node (ref "Q9") (pin "1") (pinfunction "G_1") (pintype "passive"))
      (node (ref "U2") (pin "8") (pinfunction "OUT8_8") (pintype "bidirectional"))
    )
    (net (code "44") (name "Net-(Q10-D)") (class "Default")
      (node (ref "Q10") (pin "2") (pinfunction "D_2") (pintype "passive"))
      (node (ref "U$6") (pin "3") (pinfunction "3_3") (pintype "bidirectional"))
      (node (ref "U$6") (pin "4") (pinfunction "4_4") (pintype "bidirectional"))
    )
    (net (code "45") (name "Net-(Q10-G)") (class "Default")
      (node (ref "Q10") (pin "1") (pinfunction "G_1") (pintype "passive"))
      (node (ref "U2") (pin "9") (pinfunction "OUT9_9") (pintype "bidirectional"))
    )
    (net (code "46") (name "Net-(Q11-D)") (class "Default")
      (node (ref "Q11") (pin "2") (pinfunction "D_2") (pintype "passive"))
      (node (ref "U$6") (pin "5") (pinfunction "5_5") (pintype "bidirectional"))
      (node (ref "U$6") (pin "6") (pinfunction "6_6") (pintype "bidirectional"))
    )
    (net (code "47") (name "Net-(Q11-G)") (class "Default")
      (node (ref "Q11") (pin "1") (pinfunction "G_1") (pintype "passive"))
      (node (ref "U2") (pin "10") (pinfunction "OUT10_10") (pintype "bidirectional"))
    )
    (net (code "48") (name "Net-(Q12-D)") (class "Default")
      (node (ref "Q12") (pin "2") (pinfunction "D_2") (pintype "passive"))
      (node (ref "U$6") (pin "7") (pinfunction "7_7") (pintype "bidirectional"))
      (node (ref "U$6") (pin "8") (pinfunction "8_8") (pintype "bidirectional"))
    )
    (net (code "49") (name "Net-(Q12-G)") (class "Default")
      (node (ref "Q12") (pin "1") (pinfunction "G_1") (pintype "passive"))
      (node (ref "U2") (pin "11") (pinfunction "OUT11_11") (pintype "bidirectional"))
    )
    (net (code "50") (name "Net-(Q13-D)") (class "Default")
      (node (ref "Q13") (pin "2") (pinfunction "D_2") (pintype "passive"))
      (node (ref "U$7") (pin "3") (pinfunction "3_3") (pintype "bidirectional"))
      (node (ref "U$7") (pin "4") (pinfunction "4_4") (pintype "bidirectional"))
    )
    (net (code "51") (name "Net-(Q13-G)") (class "Default")
      (node (ref "Q13") (pin "1") (pinfunction "G_1") (pintype "passive"))
      (node (ref "U2") (pin "12") (pinfunction "OUT12_12") (pintype "bidirectional"))
    )
    (net (code "52") (name "Net-(Q14-D)") (class "Default")
      (node (ref "Q14") (pin "2") (pinfunction "D_2") (pintype "passive"))
      (node (ref "U$7") (pin "5") (pinfunction "5_5") (pintype "bidirectional"))
      (node (ref "U$7") (pin "6") (pinfunction "6_6") (pintype "bidirectional"))
    )
    (net (code "53") (name "Net-(Q14-G)") (class "Default")
      (node (ref "Q14") (pin "1") (pinfunction "G_1") (pintype "passive"))
      (node (ref "U2") (pin "13") (pinfunction "OUT13_13") (pintype "bidirectional"))
    )
    (net (code "54") (name "Net-(Q15-D)") (class "Default")
      (node (ref "Q15") (pin "2") (pinfunction "D_2") (pintype "passive"))
      (node (ref "U$7") (pin "7") (pinfunction "7_7") (pintype "bidirectional"))
      (node (ref "U$7") (pin "8") (pinfunction "8_8") (pintype "bidirectional"))
    )
    (net (code "55") (name "Net-(Q15-G)") (class "Default")
      (node (ref "Q15") (pin "1") (pinfunction "G_1") (pintype "passive"))
      (node (ref "U2") (pin "14") (pinfunction "OUT14_14") (pintype "bidirectional"))
    )
    (net (code "56") (name "Net-(Q16-D)") (class "Default")
      (node (ref "Q16") (pin "2") (pinfunction "D_2") (pintype "passive"))
      (node (ref "U$9") (pin "3") (pinfunction "3_3") (pintype "bidirectional"))
      (node (ref "U$9") (pin "4") (pinfunction "4_4") (pintype "bidirectional"))
    )
    (net (code "57") (name "Net-(Q17-D)") (class "Default")
      (node (ref "Q17") (pin "2") (pinfunction "D_2") (pintype "passive"))
      (node (ref "U$9") (pin "5") (pinfunction "5_5") (pintype "bidirectional"))
      (node (ref "U$9") (pin "6") (pinfunction "6_6") (pintype "bidirectional"))
    )
    (net (code "58") (name "Net-(Q17-G)") (class "Default")
      (node (ref "Q17") (pin "1") (pinfunction "G_1") (pintype "passive"))
      (node (ref "U3") (pin "28") (pinfunction "OUT0_28") (pintype "bidirectional"))
    )
    (net (code "59") (name "Net-(Q18-D)") (class "Default")
      (node (ref "Q18") (pin "2") (pinfunction "D_2") (pintype "passive"))
      (node (ref "U$9") (pin "7") (pinfunction "7_7") (pintype "bidirectional"))
      (node (ref "U$9") (pin "8") (pinfunction "8_8") (pintype "bidirectional"))
    )
    (net (code "60") (name "Net-(Q18-G)") (class "Default")
      (node (ref "Q18") (pin "1") (pinfunction "G_1") (pintype "passive"))
      (node (ref "U3") (pin "1") (pinfunction "OUT1_1") (pintype "bidirectional"))
    )
    (net (code "61") (name "Net-(Q19-D)") (class "Default")
      (node (ref "Q19") (pin "2") (pinfunction "D_2") (pintype "passive"))
      (node (ref "U$10") (pin "3") (pinfunction "3_3") (pintype "bidirectional"))
      (node (ref "U$10") (pin "4") (pinfunction "4_4") (pintype "bidirectional"))
    )
    (net (code "62") (name "Net-(Q19-G)") (class "Default")
      (node (ref "Q19") (pin "1") (pinfunction "G_1") (pintype "passive"))
      (node (ref "U3") (pin "2") (pinfunction "OUT2_2") (pintype "bidirectional"))
    )
    (net (code "63") (name "Net-(Q20-D)") (class "Default")
      (node (ref "Q20") (pin "2") (pinfunction "D_2") (pintype "passive"))
      (node (ref "U$10") (pin "5") (pinfunction "5_5") (pintype "bidirectional"))
      (node (ref "U$10") (pin "6") (pinfunction "6_6") (pintype "bidirectional"))
    )
    (net (code "64") (name "Net-(Q20-G)") (class "Default")
      (node (ref "Q20") (pin "1") (pinfunction "G_1") (pintype "passive"))
      (node (ref "U3") (pin "3") (pinfunction "OUT3_3") (pintype "bidirectional"))
    )
    (net (code "65") (name "Net-(Q21-D)") (class "Default")
      (node (ref "Q21") (pin "2") (pinfunction "D_2") (pintype "passive"))
      (node (ref "U$10") (pin "7") (pinfunction "7_7") (pintype "bidirectional"))
      (node (ref "U$10") (pin "8") (pinfunction "8_8") (pintype "bidirectional"))
    )
    (net (code "66") (name "Net-(Q21-G)") (class "Default")
      (node (ref "Q21") (pin "1") (pinfunction "G_1") (pintype "passive"))
      (node (ref "U3") (pin "4") (pinfunction "OUT4_4") (pintype "bidirectional"))
    )
    (net (code "67") (name "Net-(Q22-D)") (class "Default")
      (node (ref "Q22") (pin "2") (pinfunction "D_2") (pintype "passive"))
      (node (ref "U$11") (pin "3") (pinfunction "3_3") (pintype "bidirectional"))
      (node (ref "U$11") (pin "4") (pinfunction "4_4") (pintype "bidirectional"))
    )
    (net (code "68") (name "Net-(Q22-G)") (class "Default")
      (node (ref "Q22") (pin "1") (pinfunction "G_1") (pintype "passive"))
      (node (ref "U3") (pin "5") (pinfunction "OUT5_5") (pintype "bidirectional"))
    )
    (net (code "69") (name "Net-(Q23-D)") (class "Default")
      (node (ref "Q23") (pin "2") (pinfunction "D_2") (pintype "passive"))
      (node (ref "U$11") (pin "5") (pinfunction "5_5") (pintype "bidirectional"))
      (node (ref "U$11") (pin "6") (pinfunction "6_6") (pintype "bidirectional"))
    )
    (net (code "70") (name "Net-(Q23-G)") (class "Default")
      (node (ref "Q23") (pin "1") (pinfunction "G_1") (pintype "passive"))
      (node (ref "U3") (pin "6") (pinfunction "OUT6_6") (pintype "bidirectional"))
    )
    (net (code "71") (name "Net-(Q24-D)") (class "Default")
      (node (ref "Q24") (pin "2") (pinfunction "D_2") (pintype "passive"))
      (node (ref "U$11") (pin "7") (pinfunction "7_7") (pintype "bidirectional"))
      (node (ref "U$11") (pin "8") (pinfunction "8_8") (pintype "bidirectional"))
    )
    (net (code "72") (name "Net-(Q24-G)") (class "Default")
      (node (ref "Q24") (pin "1") (pinfunction "G_1") (pintype "passive"))
      (node (ref "U3") (pin "7") (pinfunction "OUT7_7") (pintype "bidirectional"))
    )
    (net (code "73") (name "Net-(Q25-D)") (class "Default")
      (node (ref "Q25") (pin "2") (pinfunction "D_2") (pintype "passive"))
      (node (ref "U$12") (pin "3") (pinfunction "3_3") (pintype "bidirectional"))
      (node (ref "U$12") (pin "4") (pinfunction "4_4") (pintype "bidirectional"))
    )
    (net (code "74") (name "Net-(Q25-G)") (class "Default")
      (node (ref "Q25") (pin "1") (pinfunction "G_1") (pintype "passive"))
      (node (ref "U3") (pin "8") (pinfunction "OUT8_8") (pintype "bidirectional"))
    )
    (net (code "75") (name "Net-(Q26-D)") (class "Default")
      (node (ref "Q26") (pin "2") (pinfunction "D_2") (pintype "passive"))
      (node (ref "U$12") (pin "5") (pinfunction "5_5") (pintype "bidirectional"))
      (node (ref "U$12") (pin "6") (pinfunction "6_6") (pintype "bidirectional"))
    )
    (net (code "76") (name "Net-(Q26-G)") (class "Default")
      (node (ref "Q26") (pin "1") (pinfunction "G_1") (pintype "passive"))
      (node (ref "U3") (pin "9") (pinfunction "OUT9_9") (pintype "bidirectional"))
    )
    (net (code "77") (name "Net-(Q27-D)") (class "Default")
      (node (ref "Q27") (pin "2") (pinfunction "D_2") (pintype "passive"))
      (node (ref "U$12") (pin "7") (pinfunction "7_7") (pintype "bidirectional"))
      (node (ref "U$12") (pin "8") (pinfunction "8_8") (pintype "bidirectional"))
    )
    (net (code "78") (name "Net-(Q27-G)") (class "Default")
      (node (ref "Q27") (pin "1") (pinfunction "G_1") (pintype "passive"))
      (node (ref "U3") (pin "10") (pinfunction "OUT10_10") (pintype "bidirectional"))
    )
    (net (code "79") (name "Net-(Q28-D)") (class "Default")
      (node (ref "Q28") (pin "2") (pinfunction "D_2") (pintype "passive"))
      (node (ref "U$13") (pin "3") (pinfunction "3_3") (pintype "bidirectional"))
      (node (ref "U$13") (pin "4") (pinfunction "4_4") (pintype "bidirectional"))
    )
    (net (code "80") (name "Net-(Q28-G)") (class "Default")
      (node (ref "Q28") (pin "1") (pinfunction "G_1") (pintype "passive"))
      (node (ref "U3") (pin "11") (pinfunction "OUT11_11") (pintype "bidirectional"))
    )
    (net (code "81") (name "Net-(Q29-D)") (class "Default")
      (node (ref "Q29") (pin "2") (pinfunction "D_2") (pintype "passive"))
      (node (ref "U$13") (pin "5") (pinfunction "5_5") (pintype "bidirectional"))
      (node (ref "U$13") (pin "6") (pinfunction "6_6") (pintype "bidirectional"))
    )
    (net (code "82") (name "Net-(Q29-G)") (class "Default")
      (node (ref "Q29") (pin "1") (pinfunction "G_1") (pintype "passive"))
      (node (ref "U3") (pin "12") (pinfunction "OUT12_12") (pintype "bidirectional"))
    )
    (net (code "83") (name "Net-(Q30-D)") (class "Default")
      (node (ref "Q30") (pin "2") (pinfunction "D_2") (pintype "passive"))
      (node (ref "U$13") (pin "7") (pinfunction "7_7") (pintype "bidirectional"))
      (node (ref "U$13") (pin "8") (pinfunction "8_8") (pintype "bidirectional"))
    )
    (net (code "84") (name "Net-(Q30-G)") (class "Default")
      (node (ref "Q30") (pin "1") (pinfunction "G_1") (pintype "passive"))
      (node (ref "U3") (pin "13") (pinfunction "OUT13_13") (pintype "bidirectional"))
    )
    (net (code "85") (name "Net-(T1-B)") (class "Default")
      (node (ref "R4") (pin "1") (pinfunction "1_1") (pintype "passive"))
      (node (ref "T1") (pin "2") (pinfunction "B_2") (pintype "passive"))
    )
    (net (code "86") (name "Net-(T2-B)") (class "Default")
      (node (ref "R1") (pin "1") (pinfunction "1_1") (pintype "passive"))
      (node (ref "T2") (pin "2") (pinfunction "B_2") (pintype "passive"))
    )
    (net (code "87") (name "Net-(T3-B)") (class "Default")
      (node (ref "R7") (pin "1") (pinfunction "1_1") (pintype "passive"))
      (node (ref "T3") (pin "2") (pinfunction "B_2") (pintype "passive"))
    )
    (net (code "88") (name "Net-(T4-B)") (class "Default")
      (node (ref "R8") (pin "1") (pinfunction "1_1") (pintype "passive"))
      (node (ref "T4") (pin "2") (pinfunction "B_2") (pintype "passive"))
    )
    (net (code "89") (name "Net-(U$1-AUDIO_IN)") (class "Default")
      (node (ref "C3") (pin "2") (pinfunction "2_2") (pintype "passive"))
      (node (ref "U$1") (pin "5") (pinfunction "AUDIO_IN_5") (pintype "input"))
    )
    (net (code "90") (name "Net-(U$1-CG)") (class "Default")
      (node (ref "C2") (pin "2") (pinfunction "2_2") (pintype "passive"))
      (node (ref "U$1") (pin "6") (pinfunction "CG_6") (pintype "bidirectional"))
    )
    (net (code "91") (name "Net-(U$1-CKIN)") (class "Default")
      (node (ref "C1") (pin "2") (pinfunction "2_2") (pintype "passive"))
      (node (ref "R18") (pin "1") (pinfunction "1_1") (pintype "passive"))
      (node (ref "U$1") (pin "8") (pinfunction "CKIN_8") (pintype "bidirectional"))
    )
    (net (code "92") (name "Net-(U2-IREF)") (class "Default")
      (node (ref "R21") (pin "1") (pinfunction "1_1") (pintype "passive"))
      (node (ref "U2") (pin "20") (pinfunction "IREF_20") (pintype "bidirectional"))
    )
    (net (code "93") (name "Net-(U3-BLANK)") (class "Default")
      (node (ref "R5") (pin "1") (pinfunction "1_1") (pintype "passive"))
      (node (ref "U3") (pin "23") (pinfunction "BLANK_23") (pintype "bidirectional"))
    )
    (net (code "94") (name "Net-(U3-IREF)") (class "Default")
      (node (ref "R6") (pin "1") (pinfunction "1_1") (pintype "passive"))
      (node (ref "U3") (pin "20") (pinfunction "IREF_20") (pintype "bidirectional"))
    )
    (net (code "95") (name "V+") (class "Default")
      (node (ref "C8") (pin "1") (pinfunction "+_1") (pintype "passive"))
      (node (ref "D1") (pin "A") (pinfunction "A_A") (pintype "passive"))
      (node (ref "JP3") (pin "1") (pinfunction "1_1") (pintype "passive"))
      (node (ref "JP3") (pin "2") (pinfunction "2_2") (pintype "passive"))
      (node (ref "U$10") (pin "1") (pinfunction "1_1") (pintype "bidirectional"))
      (node (ref "U$10") (pin "2") (pinfunction "2_2") (pintype "bidirectional"))
      (node (ref "U$11") (pin "1") (pinfunction "1_1") (pintype "bidirectional"))
      (node (ref "U$11") (pin "2") (pinfunction "2_2") (pintype "bidirectional"))
      (node (ref "U$12") (pin "1") (pinfunction "1_1") (pintype "bidirectional"))
      (node (ref "U$12") (pin "2") (pinfunction "2_2") (pintype "bidirectional"))
      (node (ref "U$13") (pin "1") (pinfunction "1_1") (pintype "bidirectional"))
      (node (ref "U$13") (pin "2") (pinfunction "2_2") (pintype "bidirectional"))
      (node (ref "U$3") (pin "1") (pinfunction "1_1") (pintype "bidirectional"))
      (node (ref "U$3") (pin "2") (pinfunction "2_2") (pintype "bidirectional"))
      (node (ref "U$4") (pin "1") (pinfunction "1_1") (pintype "bidirectional"))
      (node (ref "U$4") (pin "2") (pinfunction "2_2") (pintype "bidirectional"))
      (node (ref "U$5") (pin "1") (pinfunction "1_1") (pintype "bidirectional"))
      (node (ref "U$5") (pin "2") (pinfunction "2_2") (pintype "bidirectional"))
      (node (ref "U$6") (pin "1") (pinfunction "1_1") (pintype "bidirectional"))
      (node (ref "U$6") (pin "2") (pinfunction "2_2") (pintype "bidirectional"))
      (node (ref "U$7") (pin "1") (pinfunction "1_1") (pintype "bidirectional"))
      (node (ref "U$7") (pin "2") (pinfunction "2_2") (pintype "bidirectional"))
      (node (ref "U$9") (pin "1") (pinfunction "1_1") (pintype "bidirectional"))
      (node (ref "U$9") (pin "2") (pinfunction "2_2") (pintype "bidirectional"))
    )
    (net (code "96") (name "VCC") (class "Default")
      (node (ref "C14") (pin "2") (pinfunction "2_2") (pintype "passive"))
      (node (ref "C18") (pin "2") (pinfunction "2_2") (pintype "passive"))
      (node (ref "C4") (pin "1") (pinfunction "1_1") (pintype "passive"))
      (node (ref "C6") (pin "1") (pinfunction "+_1") (pintype "passive"))
      (node (ref "C7") (pin "2") (pinfunction "2_2") (pintype "passive"))
      (node (ref "C9") (pin "2") (pinfunction "2_2") (pintype "passive"))
      (node (ref "IC1") (pin "OUT") (pinfunction "OUT_OUT") (pintype "output"))
      (node (ref "JP1") (pin "1") (pinfunction "1_1") (pintype "passive"))
      (node (ref "R10") (pin "2") (pinfunction "2_2") (pintype "passive"))
      (node (ref "R11") (pin "2") (pinfunction "2_2") (pintype "passive"))
      (node (ref "R18") (pin "2") (pinfunction "2_2") (pintype "passive"))
      (node (ref "R2") (pin "2") (pinfunction "2_2") (pintype "passive"))
      (node (ref "R3") (pin "2") (pinfunction "2_2") (pintype "passive"))
      (node (ref "R5") (pin "2") (pinfunction "2_2") (pintype "passive"))
      (node (ref "R9") (pin "2") (pinfunction "2_2") (pintype "passive"))
      (node (ref "U$1") (pin "1") (pinfunction "VDD_1") (pintype "input"))
      (node (ref "U$2") (pin "+5V") (pinfunction "+5V_+5V") (pintype "power_in"))
      (node (ref "U$2") (pin "5V") (pinfunction "VCC_5V") (pintype "power_in"))
      (node (ref "U$2") (pin "REF") (pinfunction "AREF_REF") (pintype "input"))
      (node (ref "U2") (pin "19") (pinfunction "DCPRG_19") (pintype "bidirectional"))
      (node (ref "U2") (pin "21") (pinfunction "VCC_21") (pintype "bidirectional"))
      (node (ref "U3") (pin "19") (pinfunction "DCPRG_19") (pintype "bidirectional"))
      (node (ref "U3") (pin "21") (pinfunction "VCC_21") (pintype "bidirectional"))
    )
    (net (code "97") (name "unconnected-(T1-E-Pad3)") (class "Default")
      (node (ref "T1") (pin "3") (pinfunction "E_3") (pintype "passive"))
    )
    (net (code "98") (name "unconnected-(T2-E-Pad3)") (class "Default")
      (node (ref "T2") (pin "3") (pinfunction "E_3") (pintype "passive"))
    )
    (net (code "99") (name "unconnected-(T3-E-Pad3)") (class "Default")
      (node (ref "T3") (pin "3") (pinfunction "E_3") (pintype "passive"))
    )
    (net (code "100") (name "unconnected-(T4-E-Pad3)") (class "Default")
      (node (ref "T4") (pin "3") (pinfunction "E_3") (pintype "passive"))
    )
    (net (code "101") (name "unconnected-(U$2-0,PWM,INT0-PadD0)") (class "Default")
      (node (ref "U$2") (pin "D0") (pinfunction "0,PWM,INT0_D0") (pintype "bidirectional"))
    )
    (net (code "102") (name "unconnected-(U$2-6,LED-PadD6)") (class "Default")
      (node (ref "U$2") (pin "D6") (pinfunction "6,LED_D6") (pintype "bidirectional"))
    )
    (net (code "103") (name "unconnected-(U$2-7-PadD7)") (class "Default")
      (node (ref "U$2") (pin "D7") (pinfunction "7_D7") (pintype "bidirectional"))
    )
    (net (code "104") (name "unconnected-(U$2-8-PadE0)") (class "Default")
      (node (ref "U$2") (pin "E0") (pinfunction "8_E0") (pintype "bidirectional"))
    )
    (net (code "105") (name "unconnected-(U$2-9-PadE1)") (class "Default")
      (node (ref "U$2") (pin "E1") (pinfunction "9_E1") (pintype "bidirectional"))
    )
    (net (code "106") (name "unconnected-(U$2-14,PWM-PadC4)") (class "Default")
      (node (ref "U$2") (pin "C4") (pinfunction "14,PWM_C4") (pintype "bidirectional"))
    )
    (net (code "107") (name "unconnected-(U$2-15,PWM-PadC5)") (class "Default")
      (node (ref "U$2") (pin "C5") (pinfunction "15,PWM_C5") (pintype "bidirectional"))
    )
    (net (code "108") (name "unconnected-(U$2-16,PWM-PadC6)") (class "Default")
      (node (ref "U$2") (pin "C6") (pinfunction "16,PWM_C6") (pintype "bidirectional"))
    )
    (net (code "109") (name "unconnected-(U$2-17-PadC7)") (class "Default")
      (node (ref "U$2") (pin "C7") (pinfunction "17_C7") (pintype "bidirectional"))
    )
    (net (code "110") (name "unconnected-(U$2-18,INT6-PadE6)") (class "Default")
      (node (ref "U$2") (pin "E6") (pinfunction "18,INT6_E6") (pintype "bidirectional"))
    )
    (net (code "111") (name "unconnected-(U$2-19-PadE7)") (class "Default")
      (node (ref "U$2") (pin "E7") (pinfunction "19_E7") (pintype "bidirectional"))
    )
    (net (code "112") (name "unconnected-(U$2-20-PadB0)") (class "Default")
      (node (ref "U$2") (pin "B0") (pinfunction "20_B0") (pintype "bidirectional"))
    )
    (net (code "113") (name "unconnected-(U$2-23-PadB3)") (class "Default")
      (node (ref "U$2") (pin "B3") (pinfunction "23_B3") (pintype "bidirectional"))
    )
    (net (code "114") (name "unconnected-(U$2-24,PWM-PadB4)") (class "Default")
      (node (ref "U$2") (pin "B4") (pinfunction "24,PWM_B4") (pintype "bidirectional"))
    )
    (net (code "115") (name "unconnected-(U$2-27,PWM-PadB7)") (class "Default")
      (node (ref "U$2") (pin "B7") (pinfunction "27,PWM_B7") (pintype "bidirectional"))
    )
    (net (code "116") (name "unconnected-(U$2-28-PadA0)") (class "Default")
      (node (ref "U$2") (pin "A0") (pinfunction "28_A0") (pintype "bidirectional"))
    )
    (net (code "117") (name "unconnected-(U$2-29-PadA1)") (class "Default")
      (node (ref "U$2") (pin "A1") (pinfunction "29_A1") (pintype "bidirectional"))
    )
    (net (code "118") (name "unconnected-(U$2-30-PadA2)") (class "Default")
      (node (ref "U$2") (pin "A2") (pinfunction "30_A2") (pintype "bidirectional"))
    )
    (net (code "119") (name "unconnected-(U$2-31-PadA3)") (class "Default")
      (node (ref "U$2") (pin "A3") (pinfunction "31_A3") (pintype "bidirectional"))
    )
    (net (code "120") (name "unconnected-(U$2-32-PadA4)") (class "Default")
      (node (ref "U$2") (pin "A4") (pinfunction "32_A4") (pintype "bidirectional"))
    )
    (net (code "121") (name "unconnected-(U$2-33-PadA5)") (class "Default")
      (node (ref "U$2") (pin "A5") (pinfunction "33_A5") (pintype "bidirectional"))
    )
    (net (code "122") (name "unconnected-(U$2-34-PadA6)") (class "Default")
      (node (ref "U$2") (pin "A6") (pinfunction "34_A6") (pintype "bidirectional"))
    )
    (net (code "123") (name "unconnected-(U$2-35-PadA7)") (class "Default")
      (node (ref "U$2") (pin "A7") (pinfunction "35_A7") (pintype "bidirectional"))
    )
    (net (code "124") (name "unconnected-(U$2-36,INT4-PadE4)") (class "Default")
      (node (ref "U$2") (pin "E4") (pinfunction "36,INT4_E4") (pintype "bidirectional"))
    )
    (net (code "125") (name "unconnected-(U$2-37,INT5-PadE5)") (class "Default")
      (node (ref "U$2") (pin "E5") (pinfunction "37,INT5_E5") (pintype "bidirectional"))
    )
    (net (code "126") (name "unconnected-(U$2-39,A1-PadF1)") (class "Default")
      (node (ref "U$2") (pin "F1") (pinfunction "39,A1_F1") (pintype "bidirectional"))
    )
    (net (code "127") (name "unconnected-(U$2-40,A2-PadF2)") (class "Default")
      (node (ref "U$2") (pin "F2") (pinfunction "40,A2_F2") (pintype "bidirectional"))
    )
    (net (code "128") (name "unconnected-(U$2-41,A3-PadF3)") (class "Default")
      (node (ref "U$2") (pin "F3") (pinfunction "41,A3_F3") (pintype "bidirectional"))
    )
    (net (code "129") (name "unconnected-(U$2-42,A4-PadF4)") (class "Default")
      (node (ref "U$2") (pin "F4") (pinfunction "42,A4_F4") (pintype "bidirectional"))
    )
    (net (code "130") (name "unconnected-(U$2-43,A5-PadF5)") (class "Default")
      (node (ref "U$2") (pin "F5") (pinfunction "43,A5_F5") (pintype "bidirectional"))
    )
    (net (code "131") (name "unconnected-(U$2-44,A6-PadF6)") (class "Default")
      (node (ref "U$2") (pin "F6") (pinfunction "44,A6_F6") (pintype "bidirectional"))
    )
    (net (code "132") (name "unconnected-(U$2-45,A7-PadF7)") (class "Default")
      (node (ref "U$2") (pin "F7") (pinfunction "45,A7_F7") (pintype "bidirectional"))
    )
    (net (code "133") (name "unconnected-(U$2-_RST-PadRST)") (class "Default")
      (node (ref "U$2") (pin "RST") (pinfunction "_RST_RST") (pintype "input"))
    )
    (net (code "134") (name "unconnected-(U2-XERR-Pad16)") (class "Default")
      (node (ref "U2") (pin "16") (pinfunction "XERR_16") (pintype "bidirectional"))
    )
    (net (code "135") (name "unconnected-(U3-GSCLK-Pad18)") (class "Default")
      (node (ref "U3") (pin "18") (pinfunction "GSCLK_18") (pintype "bidirectional"))
    )
    (net (code "136") (name "unconnected-(U3-OUT14-Pad14)") (class "Default")
      (node (ref "U3") (pin "14") (pinfunction "OUT14_14") (pintype "bidirectional"))
    )
    (net (code "137") (name "unconnected-(U3-OUT15-Pad15)") (class "Default")
      (node (ref "U3") (pin "15") (pinfunction "OUT15_15") (pintype "bidirectional"))
    )
    (net (code "138") (name "unconnected-(U3-SCLK-Pad25)") (class "Default")
      (node (ref "U3") (pin "25") (pinfunction "SCLK_25") (pintype "bidirectional"))
    )
    (net (code "139") (name "unconnected-(U3-SOUT-Pad17)") (class "Default")
      (node (ref "U3") (pin "17") (pinfunction "SOUT_17") (pintype "bidirectional"))
    )
    (net (code "140") (name "unconnected-(U3-XERR-Pad16)") (class "Default")
      (node (ref "U3") (pin "16") (pinfunction "XERR_16") (pintype "bidirectional"))
    )
    (net (code "141") (name "unconnected-(U3-XLAT-Pad24)") (class "Default")
      (node (ref "U3") (pin "24") (pinfunction "XLAT_24") (pintype "bidirectional"))
    )
  )
)
